# USB_C.net
KiCad netlist of a schematic drawn in Altium Designer
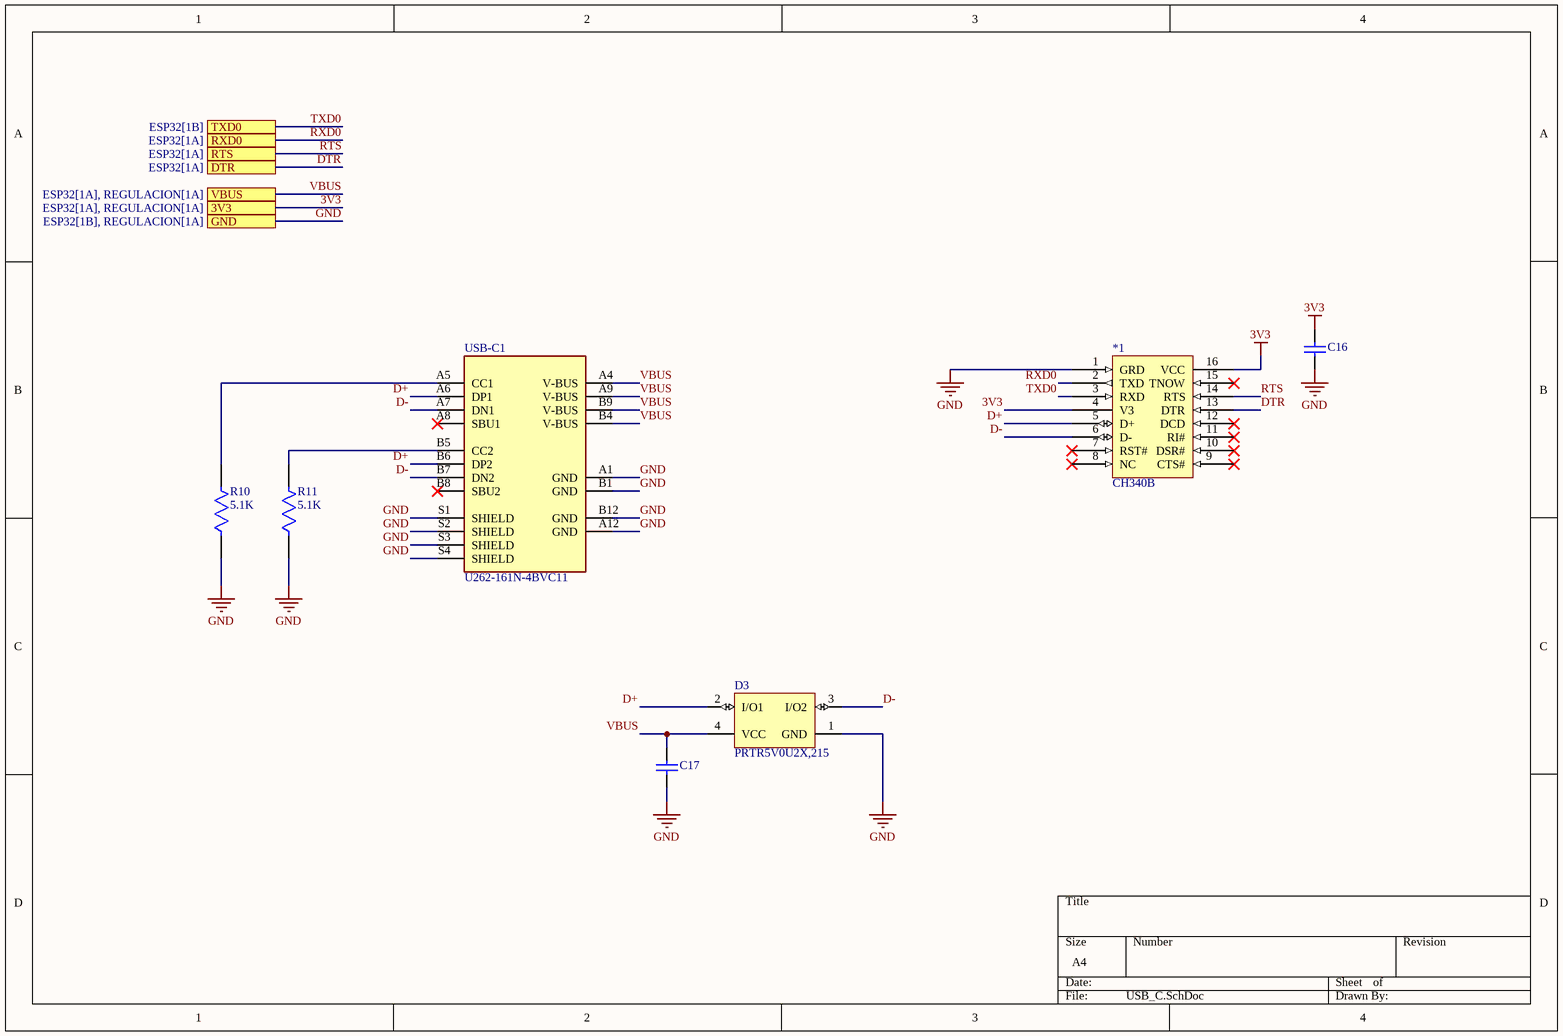
[diagram p0: USB_C.SchDoc]

(export (version "E")
  (design (tool "Eeschema 10.0.6"))
  (components
    (comp (ref "*1")
      (value "CH340B")
      (footprint "CH340B")
      (description "- USB 2.0 Transceiver 2Mbps SOP-16_150mil USB ICs ROHS")
      (libsource (lib "Isidro_Library") (part "CH340B"))
    )
    (comp (ref "C16")
      (value "08055C104KAT2A")
      (footprint "CAPC2013X94X50ML20T25")
      (description "Chip Capacitor, Ceramic, 0.1 uF, 10%, 50 V, 0805, RoHS, Tape and Reel")
      (fields (field (name "MANUFACTURER") "AVX"))
      (libsource (lib "Altium Content Vault") (part "CAP-NP-2"))
    )
    (comp (ref "C17")
      (value "08055C104KAT2A")
      (footprint "CAPC2013X94X50ML20T25")
      (description "Chip Capacitor, Ceramic, 0.1 uF, 10%, 50 V, 0805, RoHS, Tape and Reel")
      (fields (field (name "MANUFACTURER") "AVX"))
      (libsource (lib "Altium Content Vault") (part "CAP-NP-2"))
    )
    (comp (ref "D3")
      (value "PRTR5V0U2X,215")
      (footprint "NXP-SOT143B-4_V")
      (fields (field (name "MANUFACTURER") "NXP Semiconductors"))
      (libsource (lib "Altium Content Vault") (part "NXP-PRTR5V0U2X,215-4"))
    )
    (comp (ref "R10")
      (value "5.1K")
      (footprint "FP-CRCW0805-e3-MFG")
      (description "RES Thick Film, 5.1kΩ, 1%, 0.125W, 100ppm/°C, 0805")
      (fields (field (name "TOLERANCE") "1%"))
      (libsource (lib "Altium Content Vault") (part "1029c3af85768c4190bb7ad29bc67b5"))
    )
    (comp (ref "R11")
      (value "5.1K")
      (footprint "FP-CRCW0805-e3-MFG")
      (description "RES Thick Film, 5.1kΩ, 1%, 0.125W, 100ppm/°C, 0805")
      (fields (field (name "TOLERANCE") "1%"))
      (libsource (lib "Altium Content Vault") (part "1029c3af85768c4190bb7ad29bc67b5"))
    )
    (comp (ref "USB-C1")
      (value "U262-161N-4BVC11")
      (footprint "U262-161N-4BVC11")
      (description "USB - Type C Female 16 SMT USB Connectors RoHS")
      (libsource (lib "AQIMon") (part "U262-161N-4BVC11"))
    )
  )
  (nets
    (net (code "1") (name "/D+") (class "Default")
      (node (ref "*1") (pin "5") (pinfunction "D+_5") (pintype "bidirectional"))
      (node (ref "D3") (pin "2") (pinfunction "I/O1_2") (pintype "bidirectional"))
      (node (ref "USB-C1") (pin "A6") (pinfunction "DP1_A6") (pintype "power_in"))
      (node (ref "USB-C1") (pin "B6") (pinfunction "DP2_B6") (pintype "power_in"))
    )
    (net (code "2") (name "/D-") (class "Default")
      (node (ref "*1") (pin "6") (pinfunction "D-_6") (pintype "bidirectional"))
      (node (ref "D3") (pin "3") (pinfunction "I/O2_3") (pintype "bidirectional"))
      (node (ref "USB-C1") (pin "A7") (pinfunction "DN1_A7") (pintype "power_in"))
      (node (ref "USB-C1") (pin "B7") (pinfunction "DN2_B7") (pintype "power_in"))
    )
    (net (code "3") (name "/DTR") (class "Default")
      (node (ref "*1") (pin "13") (pinfunction "DTR_13") (pintype "input"))
    )
    (net (code "4") (name "/RTS") (class "Default")
      (node (ref "*1") (pin "14") (pinfunction "RTS_14") (pintype "input"))
    )
    (net (code "5") (name "/RXD0") (class "Default")
      (node (ref "*1") (pin "2") (pinfunction "TXD_2") (pintype "output"))
    )
    (net (code "6") (name "/TXD0") (class "Default")
      (node (ref "*1") (pin "3") (pinfunction "RXD_3") (pintype "input"))
    )
    (net (code "7") (name "/VBUS") (class "Default")
      (node (ref "C17") (pin "2") (pinfunction "2_2") (pintype "passive"))
      (node (ref "D3") (pin "4") (pinfunction "VCC_4") (pintype "power_in"))
      (node (ref "USB-C1") (pin "A4") (pinfunction "V-BUS_A4") (pintype "power_in"))
      (node (ref "USB-C1") (pin "A9") (pinfunction "V-BUS_A9") (pintype "power_in"))
      (node (ref "USB-C1") (pin "B4") (pinfunction "V-BUS_B4") (pintype "power_in"))
      (node (ref "USB-C1") (pin "B9") (pinfunction "V-BUS_B9") (pintype "power_in"))
    )
    (net (code "8") (name "3V3") (class "Default")
      (node (ref "*1") (pin "16") (pinfunction "VCC_16") (pintype "power_in"))
      (node (ref "*1") (pin "4") (pinfunction "V3_4") (pintype "power_in"))
      (node (ref "C16") (pin "2") (pinfunction "2_2") (pintype "passive"))
    )
    (net (code "9") (name "GND") (class "Default")
      (node (ref "*1") (pin "1") (pinfunction "GRD_1") (pintype "input"))
      (node (ref "C16") (pin "1") (pinfunction "1_1") (pintype "passive"))
      (node (ref "C17") (pin "1") (pinfunction "1_1") (pintype "passive"))
      (node (ref "D3") (pin "1") (pinfunction "GND_1") (pintype "power_in"))
      (node (ref "R10") (pin "1") (pinfunction "1_1") (pintype "passive"))
      (node (ref "R11") (pin "1") (pinfunction "1_1") (pintype "passive"))
      (node (ref "USB-C1") (pin "A1") (pinfunction "GND_A1") (pintype "power_in"))
      (node (ref "USB-C1") (pin "A12") (pinfunction "GND_A12") (pintype "power_in"))
      (node (ref "USB-C1") (pin "B1") (pinfunction "GND_B1") (pintype "power_in"))
      (node (ref "USB-C1") (pin "B12") (pinfunction "GND_B12") (pintype "power_in"))
      (node (ref "USB-C1") (pin "S1") (pinfunction "SHIELD_S1") (pintype "passive"))
      (node (ref "USB-C1") (pin "S2") (pinfunction "SHIELD_S2") (pintype "passive"))
      (node (ref "USB-C1") (pin "S3") (pinfunction "SHIELD_S3") (pintype "passive"))
      (node (ref "USB-C1") (pin "S4") (pinfunction "SHIELD_S4") (pintype "passive"))
    )
    (net (code "10") (name "Net-(USB-C1-CC1)") (class "Default")
      (node (ref "R10") (pin "2") (pinfunction "2_2") (pintype "passive"))
      (node (ref "USB-C1") (pin "A5") (pinfunction "CC1_A5") (pintype "power_in"))
    )
    (net (code "11") (name "Net-(USB-C1-CC2)") (class "Default")
      (node (ref "R11") (pin "2") (pinfunction "2_2") (pintype "passive"))
      (node (ref "USB-C1") (pin "B5") (pinfunction "CC2_B5") (pintype "power_in"))
    )
    (net (code "12") (name "unconnected-(*1-CTS#-Pad9)") (class "Default")
      (node (ref "*1") (pin "9") (pinfunction "CTS#_9") (pintype "input+no_connect"))
    )
    (net (code "13") (name "unconnected-(*1-DCD-Pad12)") (class "Default")
      (node (ref "*1") (pin "12") (pinfunction "DCD_12") (pintype "input+no_connect"))
    )
    (net (code "14") (name "unconnected-(*1-DSR#-Pad10)") (class "Default")
      (node (ref "*1") (pin "10") (pinfunction "DSR#_10") (pintype "input+no_connect"))
    )
    (net (code "15") (name "unconnected-(*1-NC-Pad8)") (class "Default")
      (node (ref "*1") (pin "8") (pinfunction "NC_8") (pintype "input+no_connect"))
    )
    (net (code "16") (name "unconnected-(*1-RI#-Pad11)") (class "Default")
      (node (ref "*1") (pin "11") (pinfunction "RI#_11") (pintype "input+no_connect"))
    )
    (net (code "17") (name "unconnected-(*1-RST#-Pad7)") (class "Default")
      (node (ref "*1") (pin "7") (pinfunction "RST#_7") (pintype "input+no_connect"))
    )
    (net (code "18") (name "unconnected-(*1-TNOW-Pad15)") (class "Default")
      (node (ref "*1") (pin "15") (pinfunction "TNOW_15") (pintype "input+no_connect"))
    )
    (net (code "19") (name "unconnected-(USB-C1-SBU1-PadA8)") (class "Default")
      (node (ref "USB-C1") (pin "A8") (pinfunction "SBU1_A8") (pintype "power_in+no_connect"))
    )
    (net (code "20") (name "unconnected-(USB-C1-SBU2-PadB8)") (class "Default")
      (node (ref "USB-C1") (pin "B8") (pinfunction "SBU2_B8") (pintype "power_in+no_connect"))
    )
  )
)
